# tweeq-FB_Audio.net
KiCad netlist of a schematic drawn in EAGLE
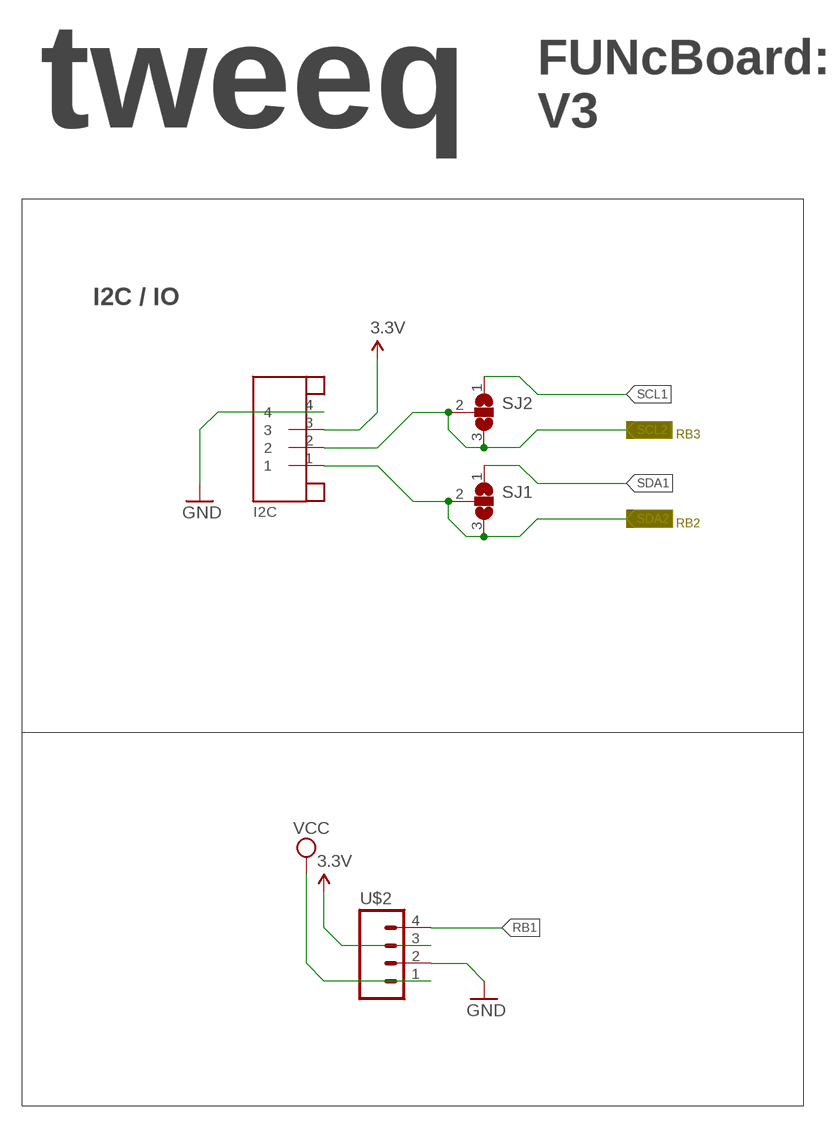
[diagram p0: schematic, sheet 1, part 1 of 2]
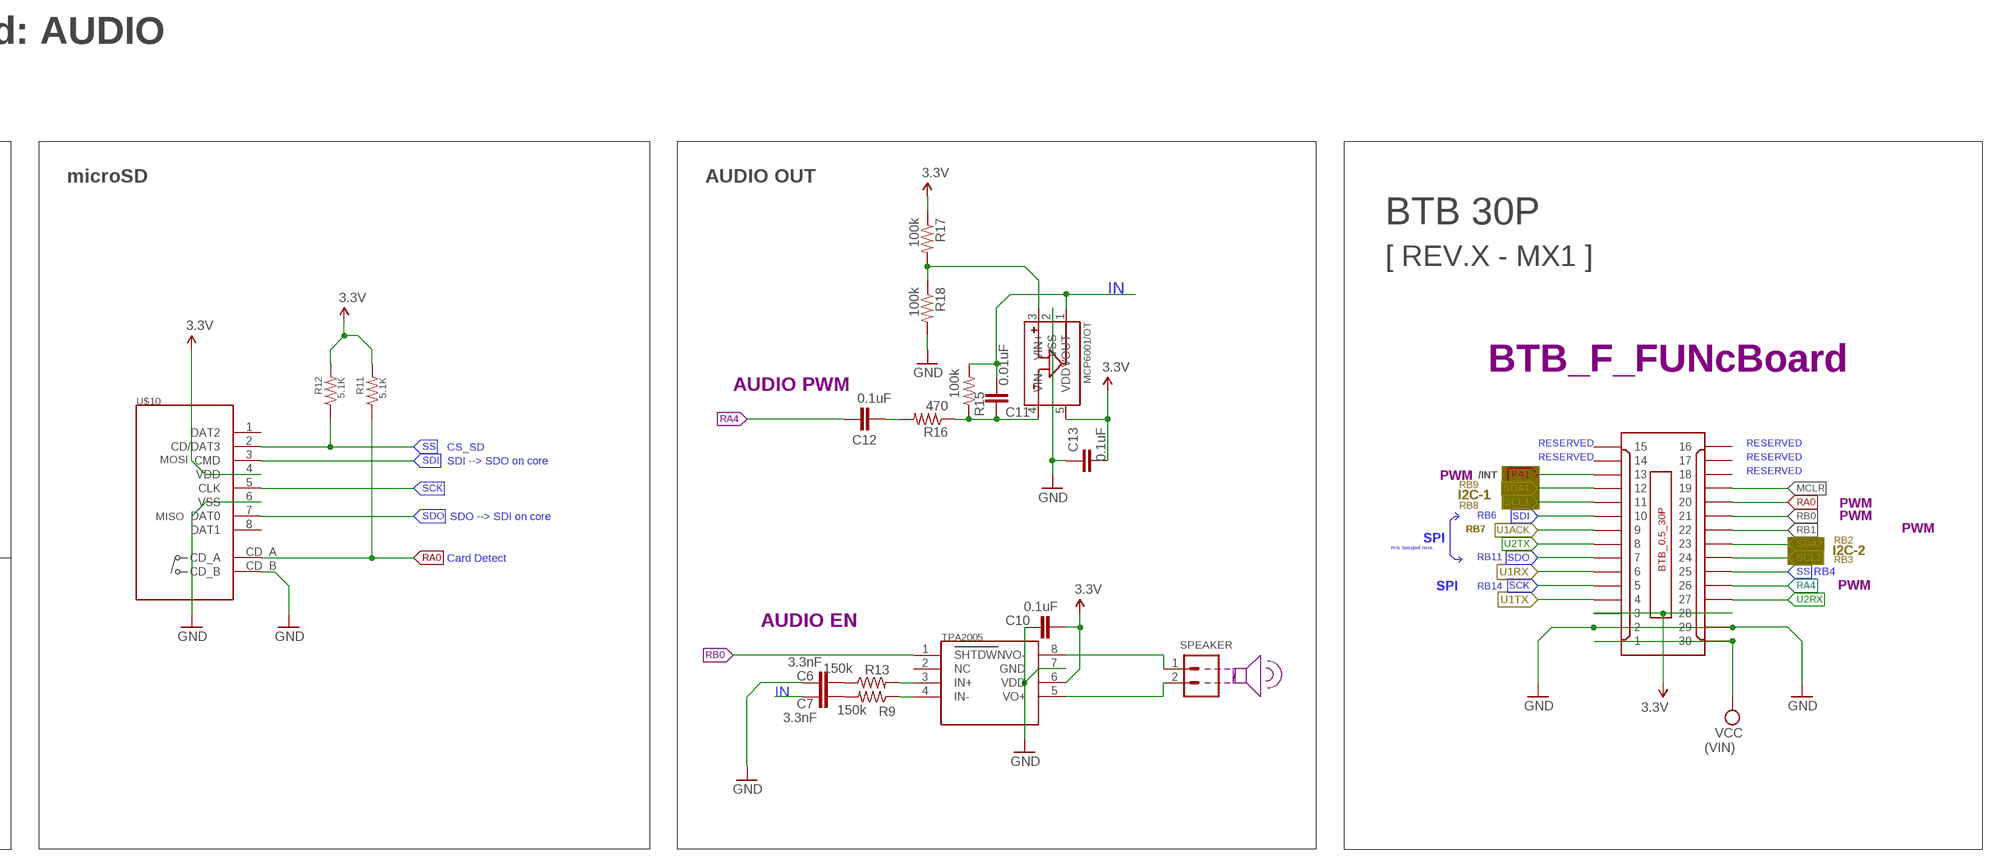
[diagram p1: schematic, sheet 1, part 2 of 2]

(export (version "E")
  (design (tool "Eeschema 10.0.6"))
  (components
    (comp (ref "C6")
      (value "3.3nF")
      (footprint "eagle-import:C0402")
      (libsource (lib "eagle-import") (part "C-EUC0402"))
    )
    (comp (ref "C7")
      (value "3.3nF")
      (footprint "eagle-import:C0402")
      (libsource (lib "eagle-import") (part "C-EUC0402"))
    )
    (comp (ref "C10")
      (value "0.1uF")
      (footprint "eagle-import:C0402")
      (libsource (lib "eagle-import") (part "C-EUC0402"))
    )
    (comp (ref "C11")
      (value "0.01uF")
      (footprint "eagle-import:C0402")
      (libsource (lib "eagle-import") (part "C-EUC0402"))
    )
    (comp (ref "C12")
      (value "0.1uF")
      (footprint "eagle-import:C0402")
      (libsource (lib "eagle-import") (part "C-EUC0402"))
    )
    (comp (ref "C13")
      (value "0.1uF")
      (footprint "eagle-import:C0402")
      (libsource (lib "eagle-import") (part "C-EUC0402"))
    )
    (comp (ref "I2C")
      (value "JST-4PINSH")
      (footprint "eagle-import:SH1.0-4PIN")
      (libsource (lib "eagle-import") (part "JST-4PINSH"))
    )
    (comp (ref "MCP6001/OT")
      (value "MCP6001/OT")
      (footprint "eagle-import:SOT23-5")
      (libsource (lib "eagle-import") (part "MCP6001/OT"))
    )
    (comp (ref "R9")
      (value "150k")
      (footprint "eagle-import:R0402")
      (libsource (lib "eagle-import") (part "R-US_R0402"))
    )
    (comp (ref "R11")
      (value "5.1K")
      (footprint "eagle-import:R0402")
      (libsource (lib "eagle-import") (part "rcl_R-US_R0402"))
    )
    (comp (ref "R12")
      (value "5.1K")
      (footprint "eagle-import:R0402")
      (libsource (lib "eagle-import") (part "rcl_R-US_R0402"))
    )
    (comp (ref "R13")
      (value "150k")
      (footprint "eagle-import:R0402")
      (libsource (lib "eagle-import") (part "R-US_R0402"))
    )
    (comp (ref "R15")
      (value "100k")
      (footprint "eagle-import:R0402")
      (libsource (lib "eagle-import") (part "R-US_R0402"))
    )
    (comp (ref "R16")
      (value "470")
      (footprint "eagle-import:0402-RES")
      (libsource (lib "eagle-import") (part "RESISTOR0402-RES"))
    )
    (comp (ref "R17")
      (value "100k")
      (footprint "eagle-import:R0402")
      (libsource (lib "eagle-import") (part "R-US_R0402"))
    )
    (comp (ref "R18")
      (value "100k")
      (footprint "eagle-import:R0402")
      (libsource (lib "eagle-import") (part "R-US_R0402"))
    )
    (comp (ref "SJ1")
      (value "JUMPER_SJ2WS")
      (footprint "eagle-import:JUMPER_SJ_S")
      (libsource (lib "eagle-import") (part "JUMPER_SJ2WS"))
    )
    (comp (ref "SJ2")
      (value "JUMPER_SJ2WS")
      (footprint "eagle-import:JUMPER_SJ_S")
      (libsource (lib "eagle-import") (part "JUMPER_SJ2WS"))
    )
    (comp (ref "SPEAKER")
      (value "LOUDSPEAKER")
      (footprint "eagle-import:1X02")
      (libsource (lib "eagle-import") (part "M02PTH"))
    )
    (comp (ref "TPA2005")
      (value "TPA2005")
      (footprint "eagle-import:MSOP8")
      (libsource (lib "eagle-import") (part "TPA2005"))
    )
    (comp (ref "U$1")
      (value "BTB_CONN_30P/F")
      (footprint "eagle-import:BTB0.5-30F-3.0G")
      (libsource (lib "eagle-import") (part "BTB_CONN_30P/F"))
    )
    (comp (ref "U$2")
      (value "M04")
      (footprint "eagle-import:1X04_PAD")
      (libsource (lib "eagle-import") (part "M04"))
    )
    (comp (ref "U$10")
      (value "MICROSD_DM3D")
      (footprint "eagle-import:DM3D-SF")
      (libsource (lib "eagle-import") (part "MICROSD_DM3D"))
    )
  )
  (nets
    (net (code "1") (name "/IN") (class "Default")
      (node (ref "C11") (pin "2") (pinfunction "2_2") (pintype "passive"))
      (node (ref "C7") (pin "2") (pinfunction "2_2") (pintype "passive"))
      (node (ref "MCP6001/OT") (pin "1") (pinfunction "VOUT_1") (pintype "bidirectional"))
      (node (ref "R15") (pin "2") (pinfunction "2_2") (pintype "passive"))
    )
    (net (code "2") (name "3.3V") (class "Default")
      (node (ref "C10") (pin "2") (pinfunction "2_2") (pintype "passive"))
      (node (ref "C13") (pin "2") (pinfunction "2_2") (pintype "passive"))
      (node (ref "I2C") (pin "3") (pinfunction "3_3") (pintype "bidirectional"))
      (node (ref "MCP6001/OT") (pin "5") (pinfunction "VDD_5") (pintype "bidirectional"))
      (node (ref "R11") (pin "2") (pinfunction "2_2") (pintype "passive"))
      (node (ref "R12") (pin "2") (pinfunction "2_2") (pintype "passive"))
      (node (ref "R17") (pin "1") (pinfunction "1_1") (pintype "passive"))
      (node (ref "TPA2005") (pin "6") (pinfunction "VDD_6") (pintype "bidirectional"))
      (node (ref "U$1") (pin "28") (pinfunction "28_28") (pintype "bidirectional"))
      (node (ref "U$1") (pin "3") (pinfunction "3_3") (pintype "bidirectional"))
      (node (ref "U$10") (pin "4") (pinfunction "VDD_4") (pintype "power_in"))
      (node (ref "U$2") (pin "3") (pinfunction "3_3") (pintype "passive"))
    )
    (net (code "3") (name "GND") (class "Default")
      (node (ref "C10") (pin "1") (pinfunction "1_1") (pintype "passive"))
      (node (ref "C13") (pin "1") (pinfunction "1_1") (pintype "passive"))
      (node (ref "C6") (pin "1") (pinfunction "1_1") (pintype "passive"))
      (node (ref "I2C") (pin "4") (pinfunction "4_4") (pintype "bidirectional"))
      (node (ref "MCP6001/OT") (pin "2") (pinfunction "VSS_2") (pintype "bidirectional"))
      (node (ref "R18") (pin "2") (pinfunction "2_2") (pintype "passive"))
      (node (ref "TPA2005") (pin "7") (pinfunction "GND_7") (pintype "bidirectional"))
      (node (ref "U$1") (pin "2") (pinfunction "2_2") (pintype "bidirectional"))
      (node (ref "U$1") (pin "29") (pinfunction "29_29") (pintype "bidirectional"))
      (node (ref "U$10") (pin "6") (pinfunction "VSS_6") (pintype "bidirectional"))
      (node (ref "U$10") (pin "CD_B") (pinfunction "CD_B_CD_B") (pintype "bidirectional"))
      (node (ref "U$2") (pin "2") (pinfunction "2_2") (pintype "passive"))
    )
    (net (code "4") (name "MCLR") (class "Default")
      (node (ref "U$1") (pin "19") (pinfunction "19_19") (pintype "bidirectional"))
    )
    (net (code "5") (name "Net-(C6-Pad2)") (class "Default")
      (node (ref "C6") (pin "2") (pinfunction "2_2") (pintype "passive"))
      (node (ref "R13") (pin "1") (pinfunction "1_1") (pintype "passive"))
    )
    (net (code "6") (name "Net-(C7-Pad1)") (class "Default")
      (node (ref "C7") (pin "1") (pinfunction "1_1") (pintype "passive"))
      (node (ref "R9") (pin "2") (pinfunction "2_2") (pintype "passive"))
    )
    (net (code "7") (name "Net-(C12-Pad2)") (class "Default")
      (node (ref "C12") (pin "2") (pinfunction "2_2") (pintype "passive"))
      (node (ref "R16") (pin "2") (pinfunction "2_2") (pintype "passive"))
    )
    (net (code "8") (name "Net-(MCP6001/OT-VIN+)") (class "Default")
      (node (ref "MCP6001/OT") (pin "3") (pinfunction "VIN+_3") (pintype "bidirectional"))
      (node (ref "R17") (pin "2") (pinfunction "2_2") (pintype "passive"))
      (node (ref "R18") (pin "1") (pinfunction "1_1") (pintype "passive"))
    )
    (net (code "9") (name "Net-(MCP6001/OT-VIN-)") (class "Default")
      (node (ref "C11") (pin "1") (pinfunction "1_1") (pintype "passive"))
      (node (ref "MCP6001/OT") (pin "4") (pinfunction "VIN-_4") (pintype "bidirectional"))
      (node (ref "R15") (pin "1") (pinfunction "1_1") (pintype "passive"))
      (node (ref "R16") (pin "1") (pinfunction "1_1") (pintype "passive"))
    )
    (net (code "10") (name "Net-(TPA2005-IN+)") (class "Default")
      (node (ref "R13") (pin "2") (pinfunction "2_2") (pintype "passive"))
      (node (ref "TPA2005") (pin "3") (pinfunction "IN+_3") (pintype "bidirectional"))
    )
    (net (code "11") (name "Net-(TPA2005-IN-)") (class "Default")
      (node (ref "R9") (pin "1") (pinfunction "1_1") (pintype "passive"))
      (node (ref "TPA2005") (pin "4") (pinfunction "IN-_4") (pintype "bidirectional"))
    )
    (net (code "12") (name "Net-(TPA2005-VO+)") (class "Default")
      (node (ref "SPEAKER") (pin "2") (pinfunction "2_2") (pintype "passive"))
      (node (ref "TPA2005") (pin "5") (pinfunction "VO+_5") (pintype "bidirectional"))
    )
    (net (code "13") (name "Net-(TPA2005-VO-)") (class "Default")
      (node (ref "SPEAKER") (pin "1") (pinfunction "1_1") (pintype "passive"))
      (node (ref "TPA2005") (pin "8") (pinfunction "VO-_8") (pintype "bidirectional"))
    )
    (net (code "14") (name "RA0") (class "Default")
      (node (ref "R11") (pin "1") (pinfunction "1_1") (pintype "passive"))
      (node (ref "U$1") (pin "20") (pinfunction "20_20") (pintype "bidirectional"))
      (node (ref "U$10") (pin "CD_A") (pinfunction "CD_A_CD_A") (pintype "bidirectional"))
    )
    (net (code "15") (name "RA1") (class "Default")
      (node (ref "U$1") (pin "13") (pinfunction "13_13") (pintype "bidirectional"))
    )
    (net (code "16") (name "RA4") (class "Default")
      (node (ref "C12") (pin "1") (pinfunction "1_1") (pintype "passive"))
      (node (ref "U$1") (pin "26") (pinfunction "26_26") (pintype "bidirectional"))
    )
    (net (code "17") (name "RB0") (class "Default")
      (node (ref "TPA2005") (pin "1") (pinfunction "SHTDWN_1") (pintype "bidirectional"))
      (node (ref "U$1") (pin "21") (pinfunction "21_21") (pintype "bidirectional"))
    )
    (net (code "18") (name "RB1") (class "Default")
      (node (ref "U$1") (pin "22") (pinfunction "22_22") (pintype "bidirectional"))
      (node (ref "U$2") (pin "4") (pinfunction "4_4") (pintype "passive"))
    )
    (net (code "19") (name "SCK") (class "Default")
      (node (ref "U$1") (pin "5") (pinfunction "5_5") (pintype "bidirectional"))
      (node (ref "U$10") (pin "5") (pinfunction "CLK_5") (pintype "bidirectional"))
    )
    (net (code "20") (name "SCL1") (class "Default")
      (node (ref "SJ2") (pin "1") (pinfunction "1_1") (pintype "passive"))
      (node (ref "U$1") (pin "11") (pinfunction "11_11") (pintype "bidirectional"))
    )
    (net (code "21") (name "SCL2") (class "Default")
      (node (ref "I2C") (pin "2") (pinfunction "2_2") (pintype "bidirectional"))
      (node (ref "SJ2") (pin "2") (pinfunction "2_2") (pintype "passive"))
      (node (ref "SJ2") (pin "3") (pinfunction "3_3") (pintype "passive"))
      (node (ref "U$1") (pin "24") (pinfunction "24_24") (pintype "bidirectional"))
    )
    (net (code "22") (name "SDA1") (class "Default")
      (node (ref "SJ1") (pin "1") (pinfunction "1_1") (pintype "passive"))
      (node (ref "U$1") (pin "12") (pinfunction "12_12") (pintype "bidirectional"))
    )
    (net (code "23") (name "SDA2") (class "Default")
      (node (ref "I2C") (pin "1") (pinfunction "1_1") (pintype "bidirectional"))
      (node (ref "SJ1") (pin "2") (pinfunction "2_2") (pintype "passive"))
      (node (ref "SJ1") (pin "3") (pinfunction "3_3") (pintype "passive"))
      (node (ref "U$1") (pin "23") (pinfunction "23_23") (pintype "bidirectional"))
    )
    (net (code "24") (name "SDI") (class "Default")
      (node (ref "U$1") (pin "10") (pinfunction "10_10") (pintype "bidirectional"))
      (node (ref "U$10") (pin "3") (pinfunction "CMD_3") (pintype "bidirectional"))
    )
    (net (code "25") (name "SDO") (class "Default")
      (node (ref "U$1") (pin "7") (pinfunction "7_7") (pintype "bidirectional"))
      (node (ref "U$10") (pin "7") (pinfunction "DAT0_7") (pintype "bidirectional"))
    )
    (net (code "26") (name "SS") (class "Default")
      (node (ref "R12") (pin "1") (pinfunction "1_1") (pintype "passive"))
      (node (ref "U$1") (pin "25") (pinfunction "25_25") (pintype "bidirectional"))
      (node (ref "U$10") (pin "2") (pinfunction "CD/DAT3_2") (pintype "bidirectional"))
    )
    (net (code "27") (name "U1ACK") (class "Default")
      (node (ref "U$1") (pin "9") (pinfunction "9_9") (pintype "bidirectional"))
    )
    (net (code "28") (name "U1RX") (class "Default")
      (node (ref "U$1") (pin "6") (pinfunction "6_6") (pintype "bidirectional"))
    )
    (net (code "29") (name "U1TX") (class "Default")
      (node (ref "U$1") (pin "4") (pinfunction "4_4") (pintype "bidirectional"))
    )
    (net (code "30") (name "U2RX") (class "Default")
      (node (ref "U$1") (pin "27") (pinfunction "27_27") (pintype "bidirectional"))
    )
    (net (code "31") (name "U2TX") (class "Default")
      (node (ref "U$1") (pin "8") (pinfunction "8_8") (pintype "bidirectional"))
    )
    (net (code "32") (name "VCC") (class "Default")
      (node (ref "U$1") (pin "1") (pinfunction "1_1") (pintype "bidirectional"))
      (node (ref "U$1") (pin "30") (pinfunction "30_30") (pintype "bidirectional"))
      (node (ref "U$2") (pin "1") (pinfunction "1_1") (pintype "passive"))
    )
    (net (code "33") (name "unconnected-(TPA2005-NC-Pad2)") (class "Default")
      (node (ref "TPA2005") (pin "2") (pinfunction "NC_2") (pintype "no_connect"))
    )
    (net (code "34") (name "unconnected-(U$1-Pad14)") (class "Default")
      (node (ref "U$1") (pin "14") (pinfunction "14_14") (pintype "bidirectional"))
    )
    (net (code "35") (name "unconnected-(U$1-Pad15)") (class "Default")
      (node (ref "U$1") (pin "15") (pinfunction "15_15") (pintype "bidirectional"))
    )
    (net (code "36") (name "unconnected-(U$1-Pad16)") (class "Default")
      (node (ref "U$1") (pin "16") (pinfunction "16_16") (pintype "bidirectional"))
    )
    (net (code "37") (name "unconnected-(U$1-Pad17)") (class "Default")
      (node (ref "U$1") (pin "17") (pinfunction "17_17") (pintype "bidirectional"))
    )
    (net (code "38") (name "unconnected-(U$1-Pad18)") (class "Default")
      (node (ref "U$1") (pin "18") (pinfunction "18_18") (pintype "bidirectional"))
    )
    (net (code "39") (name "unconnected-(U$10-DAT1-Pad8)") (class "Default")
      (node (ref "U$10") (pin "8") (pinfunction "DAT1_8") (pintype "bidirectional"))
    )
    (net (code "40") (name "unconnected-(U$10-DAT2-Pad1)") (class "Default")
      (node (ref "U$10") (pin "1") (pinfunction "DAT2_1") (pintype "bidirectional"))
    )
  )
)
